# TestingChargeController.net
KiCad netlist of a schematic drawn in Altium Designer
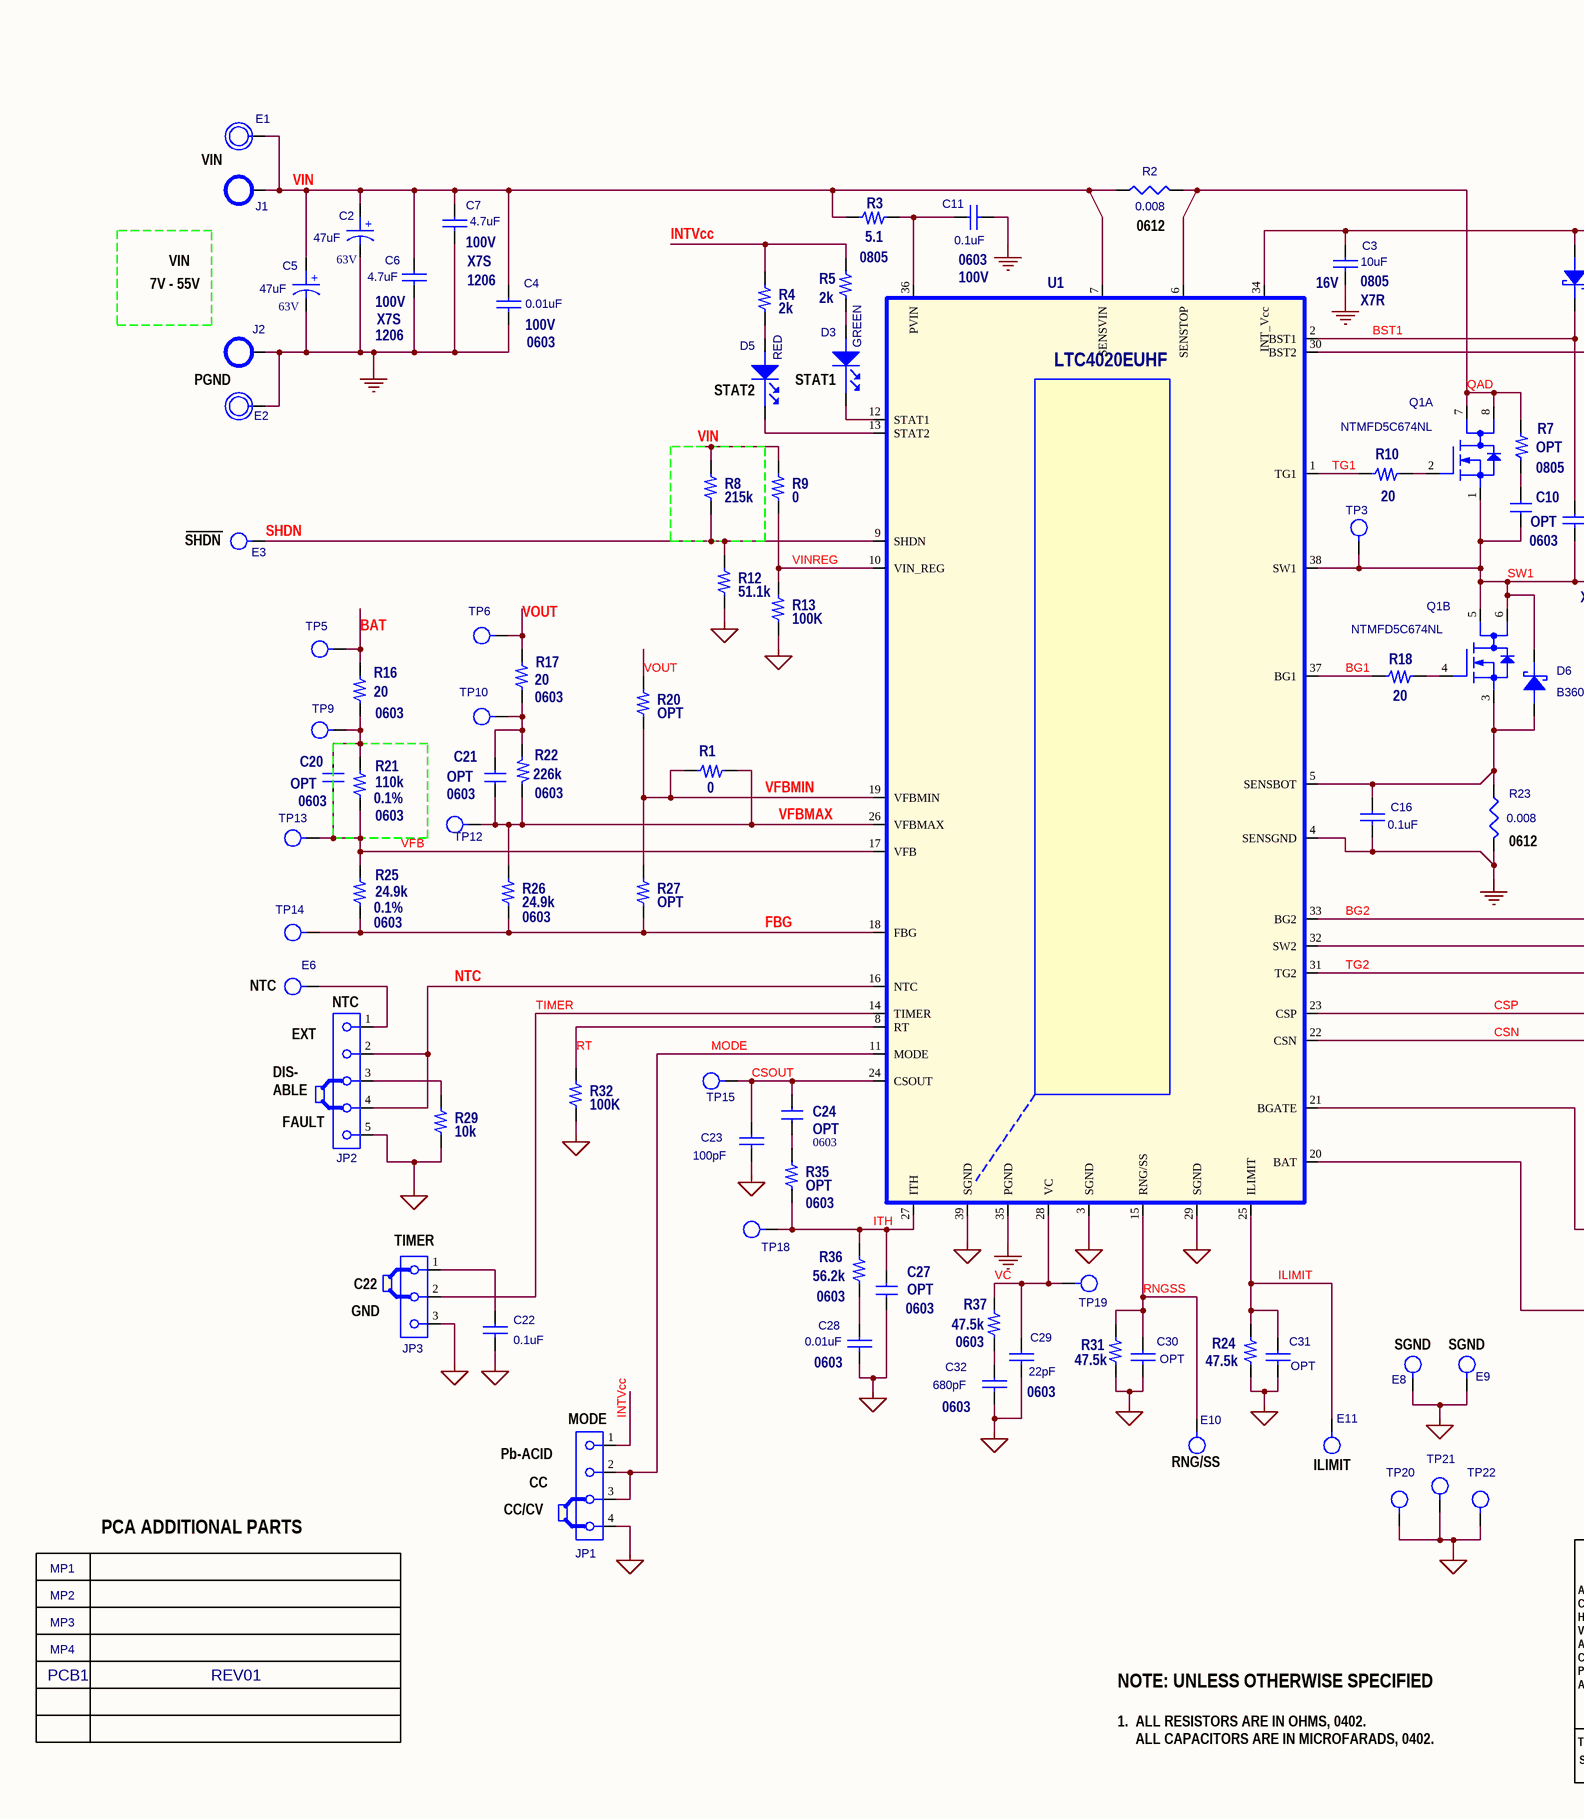
[diagram p0: TestingChargeController.SchDoc, left]
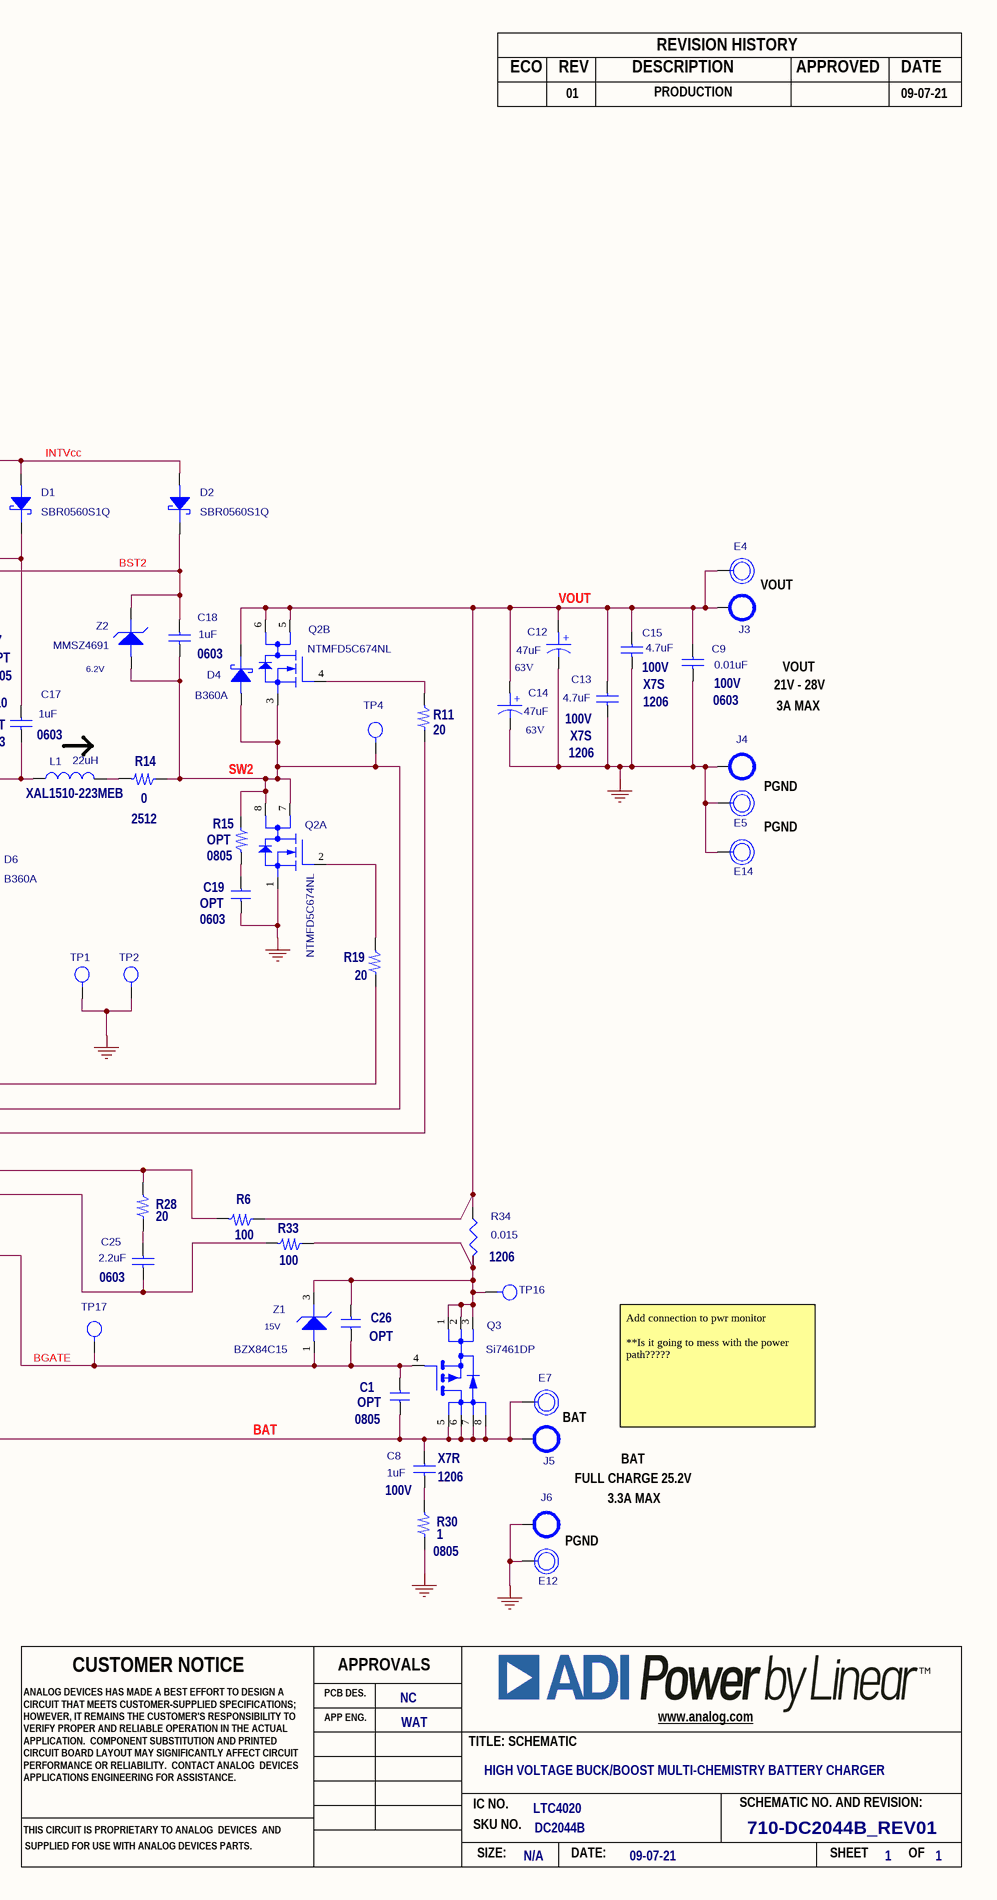
[diagram p1: TestingChargeController.SchDoc, right]

(export (version "E")
  (design (tool "Eeschema 10.0.6"))
  (components
    (comp (ref "*")
      (value "~")
      (fields
        (field (name "SKU#") "DC2044B")
        (field (name "SIZE") "N/A")
        (field (name "PAGE NUMBER") "1")
        (field (name "PAGE COUNT") "1")
        (field (name "PCB DESIGNER") "NC")
        (field (name "PCA SCHEMATIC") "710-DC2044B_REV01")
        (field (name "IC NO.") "LTC4020")
        (field (name "DATE") "09-07-21")
        (field (name "APP. ENG.") "WAT")
        (field (name "TITLE") "HIGH VOLTAGE BUCK/BOOST MULTI-CHEMISTRY BATTERY CHARGER")
      )
      (libsource (lib "*") (part "TITLEBLK_REV09_2"))
    )
    (comp (ref "C1")
      (value "OPT")
      (footprint "CC0805N")
      (description "CAP., OPTION, 0805")
      (fields (field (name "PACKAGE SIZE") "0805") (field (name "PART_NUMBER") "150-3036"))
      (libsource (lib "*") (part "CAP_ALT"))
    )
    (comp (ref "C2")
      (value "47uF")
      (footprint "PANASONIC_ZA_8X10.2")
      (description "CAP.,47uF,ALUM ELECT.,63V,20%,SMD,8.0x10.2 mm,AEC-Q200")
      (fields
        (field (name "PART_NUMBER") "150-0969")
        (field (name "TOLERANCE") "20%")
        (field (name "RATED VOLTAGE") "63V")
      )
      (libsource (lib "*") (part "CAP_P_ALT"))
    )
    (comp (ref "C3")
      (value "10uF")
      (footprint "CC0805N")
      (description "CAP.,10uF,X7R,16V,10%,0805")
      (fields
        (field (name "MANUFACTURER") "TAIYO YUDEN")
        (field (name "RATED VOLTAGE") "16V")
        (field (name "TOLERANCE") "10%")
        (field (name "DIELECTRIC TYPE") "X7R")
        (field (name "PACKAGE SIZE") "0805")
      )
      (libsource (lib "*") (part "CAP"))
    )
    (comp (ref "C4")
      (value "0.01uF")
      (footprint "CC0603N")
      (description "CAP.,0.01uF,X7R,100V,10%,0603,AEC-Q200")
      (fields
        (field (name "MANUFACTURER") "MURATA")
        (field (name "RATED VOLTAGE") "100V")
        (field (name "TOLERANCE") "10%")
        (field (name "PACKAGE SIZE") "0603")
      )
      (libsource (lib "*") (part "CAP"))
    )
    (comp (ref "C5")
      (value "47uF")
      (footprint "PANASONIC_ZA_8X10.2")
      (description "CAP.,47uF,ALUM ELECT.,63V,20%,SMD,8.0x10.2 mm,AEC-Q200")
      (fields
        (field (name "MANUFACTURER") "PANASONIC")
        (field (name "RATED VOLTAGE") "63V")
        (field (name "TOLERANCE") "20%")
      )
      (libsource (lib "*") (part "CAP_P_ALT"))
    )
    (comp (ref "C6")
      (value "4.7uF")
      (footprint "CC1206N")
      (description "CAP.,4.7uF,X7S,100V,20%,1206")
      (fields
        (field (name "PART_NUMBER") "150-2278")
        (field (name "PACKAGE SIZE") "1206")
        (field (name "DIELECTRIC TYPE") "X7S")
        (field (name "TOLERANCE") "20%")
        (field (name "RATED VOLTAGE") "100V")
      )
      (libsource (lib "*") (part "CAP"))
    )
    (comp (ref "C7")
      (value "4.7uF")
      (footprint "CC1206N")
      (description "CAP.,4.7uF,X7S,100V,20%,1206")
      (fields
        (field (name "PART_NUMBER") "150-2278")
        (field (name "PACKAGE SIZE") "1206")
        (field (name "DIELECTRIC TYPE") "X7S")
        (field (name "TOLERANCE") "20%")
        (field (name "RATED VOLTAGE") "100V")
      )
      (libsource (lib "*") (part "CAP"))
    )
    (comp (ref "C8")
      (value "1uF")
      (footprint "CC1206N")
      (description "CAP.,1uF,X7R,100V,10%,1206,AEC-Q200")
      (fields
        (field (name "MANUFACTURER") "TDK")
        (field (name "RATED VOLTAGE") "100V")
        (field (name "TOLERANCE") "10%")
        (field (name "TEMPERATURE COEFFICIENT") "X7R")
        (field (name "PACKAGE SIZE") "1206")
      )
      (libsource (lib "*") (part "CAP"))
    )
    (comp (ref "C9")
      (value "0.01uF")
      (footprint "CC0603N")
      (description "CAP.,0.01uF,X7R,100V,10%,0603,AEC-Q200")
      (fields
        (field (name "MANUFACTURER") "MURATA")
        (field (name "RATED VOLTAGE") "100V")
        (field (name "TOLERANCE") "10%")
        (field (name "PACKAGE SIZE") "0603")
      )
      (libsource (lib "*") (part "CAP"))
    )
    (comp (ref "C10")
      (value "OPT")
      (footprint "CC0603N")
      (description "CAP., OPTION, 0603")
      (fields (field (name "PACKAGE SIZE") "0603") (field (name "PART_NUMBER") "150-3038"))
      (libsource (lib "*") (part "CAP_ALT"))
    )
    (comp (ref "C11")
      (value "0.1uF")
      (footprint "CC0603N")
      (description "CAP.,0.1uF,X7R,100V,10%,0603,AEC-Q200")
      (fields
        (field (name "MANUFACTURER") "TAIYO YUDEN")
        (field (name "RATED VOLTAGE") "100V")
        (field (name "TOLERANCE") "10%")
        (field (name "PACKAGE SIZE") "0603")
      )
      (libsource (lib "*") (part "CAP"))
    )
    (comp (ref "C12")
      (value "47uF")
      (footprint "PANASONIC_ZA_8X10.2")
      (description "CAP.,47uF,ALUM ELECT.,63V,20%,SMD,8.0x10.2 mm,AEC-Q200")
      (fields
        (field (name "PART_NUMBER") "150-0969")
        (field (name "TOLERANCE") "20%")
        (field (name "RATED VOLTAGE") "63V")
      )
      (libsource (lib "*") (part "CAP_P_ALT"))
    )
    (comp (ref "C13")
      (value "4.7uF")
      (footprint "CC1206N")
      (description "CAP.,4.7uF,X7S,100V,20%,1206")
      (fields
        (field (name "MANUFACTURER") "AVX")
        (field (name "RATED VOLTAGE") "100V")
        (field (name "TOLERANCE") "20%")
        (field (name "DIELECTRIC TYPE") "X7S")
        (field (name "PACKAGE SIZE") "1206")
      )
      (libsource (lib "*") (part "CAP"))
    )
    (comp (ref "C14")
      (value "47uF")
      (footprint "PANASONIC_ZA_8X10.2")
      (description "CAP.,47uF,ALUM ELECT.,63V,20%,SMD,8.0x10.2 mm,AEC-Q200")
      (fields
        (field (name "PART_NUMBER") "150-0969")
        (field (name "TOLERANCE") "20%")
        (field (name "RATED VOLTAGE") "63V")
      )
      (libsource (lib "*") (part "CAP_P_ALT"))
    )
    (comp (ref "C15")
      (value "4.7uF")
      (footprint "CC1206N")
      (description "CAP.,4.7uF,X7S,100V,20%,1206")
      (fields
        (field (name "PART_NUMBER") "150-2278")
        (field (name "PACKAGE SIZE") "1206")
        (field (name "DIELECTRIC TYPE") "X7S")
        (field (name "TOLERANCE") "20%")
        (field (name "RATED VOLTAGE") "100V")
      )
      (libsource (lib "*") (part "CAP"))
    )
    (comp (ref "C16")
      (value "0.1uF")
      (footprint "CC0402N")
      (description "CAP.,0.1uF,X7R,16V,10%,0402,AEC-Q200")
      (fields (field (name "PART_NUMBER") "150-0506") (field (name "TOLERANCE") "10%"))
      (libsource (lib "*") (part "CAP"))
    )
    (comp (ref "C17")
      (value "1uF")
      (footprint "CC0603N")
      (description "CAP.,1uF,X7R,16V,10%,0603")
      (fields
        (field (name "MANUFACTURER") "KEMET")
        (field (name "TOLERANCE") "10%")
        (field (name "PACKAGE SIZE") "0603")
      )
      (libsource (lib "*") (part "CAP"))
    )
    (comp (ref "C18")
      (value "1uF")
      (footprint "CC0603N")
      (description "CAP.,1uF,X7R,16V,10%,0603")
      (fields
        (field (name "MANUFACTURER") "KEMET")
        (field (name "TOLERANCE") "10%")
        (field (name "PACKAGE SIZE") "0603")
      )
      (libsource (lib "*") (part "CAP"))
    )
    (comp (ref "C19")
      (value "OPT")
      (footprint "CC0603N")
      (description "CAP., OPTION, 0603")
      (fields (field (name "PACKAGE SIZE") "0603") (field (name "PART_NUMBER") "150-3038"))
      (libsource (lib "*") (part "CAP_ALT"))
    )
    (comp (ref "C20")
      (value "OPT")
      (footprint "CC0603N")
      (description "CAP., OPTION, 0603")
      (fields (field (name "PACKAGE SIZE") "0603") (field (name "PART_NUMBER") "150-3038"))
      (libsource (lib "*") (part "CAP_ALT"))
    )
    (comp (ref "C21")
      (value "OPT")
      (footprint "CC0603N")
      (description "CAP., OPTION, 0603")
      (fields (field (name "PACKAGE SIZE") "0603") (field (name "PART_NUMBER") "150-3038"))
      (libsource (lib "*") (part "CAP_ALT"))
    )
    (comp (ref "C22")
      (value "0.1uF")
      (footprint "CC0402N")
      (description "CAP.,0.1uF,X7R,16V,10%,0402,AEC-Q200")
      (fields (field (name "MANUFACTURER") "MURATA") (field (name "TOLERANCE") "10%"))
      (libsource (lib "*") (part "CAP"))
    )
    (comp (ref "C23")
      (value "100pF")
      (footprint "CC0402N")
      (description "CAP.,100pF,C0G,50V,5%,0402")
      (fields (field (name "PART_NUMBER") "150-0115") (field (name "TOLERANCE") "5%"))
      (libsource (lib "*") (part "CAP"))
    )
    (comp (ref "C24")
      (value "OPT")
      (footprint "CC0603N")
      (description "CAP., OPTION, 0603")
      (fields (field (name "PART_NUMBER") "150-3038") (field (name "PACKAGE SIZE") "0603"))
      (libsource (lib "*") (part "CAP_ALT"))
    )
    (comp (ref "C25")
      (value "2.2uF")
      (footprint "CC0603N")
      (description "CAP.,2.2uF,X7R,10V,10%,0603")
      (fields
        (field (name "MANUFACTURER") "MURATA")
        (field (name "TOLERANCE") "10%")
        (field (name "PACKAGE SIZE") "0603")
      )
      (libsource (lib "*") (part "CAP"))
    )
    (comp (ref "C26")
      (value "OPT")
      (footprint "CC0603N")
      (description "CAP., OPTION, 0603")
      (fields (field (name "PART_NUMBER") "150-3038"))
      (libsource (lib "*") (part "CAP_ALT"))
    )
    (comp (ref "C27")
      (value "OPT")
      (footprint "CC0603N")
      (description "CAP., OPTION, 0603")
      (fields (field (name "PART_NUMBER") "150-3038") (field (name "PACKAGE SIZE") "0603"))
      (libsource (lib "*") (part "CAP_ALT"))
    )
    (comp (ref "C28")
      (value "0.01uF")
      (footprint "CC0603N")
      (description "CAP.,0.01uF,X7R,50V,10%,0603")
      (fields
        (field (name "MANUFACTURER") "AVX")
        (field (name "TOLERANCE") "10%")
        (field (name "PACKAGE SIZE") "0603")
      )
      (libsource (lib "*") (part "CAP"))
    )
    (comp (ref "C29")
      (value "22pF")
      (footprint "CC0603N")
      (description "CAP.,22pF,C0G,25V,10%,0603")
      (fields
        (field (name "MANUFACTURER") "AVX")
        (field (name "TOLERANCE") "10%")
        (field (name "PACKAGE SIZE") "0603")
      )
      (libsource (lib "*") (part "CAP"))
    )
    (comp (ref "C30")
      (value "OPT")
      (footprint "CC0402N")
      (description "CAP., OPTION, 0402")
      (fields (field (name "PART_NUMBER") "150-3148"))
      (libsource (lib "*") (part "CAP"))
    )
    (comp (ref "C31")
      (value "OPT")
      (footprint "CC0402N")
      (description "CAP., OPTION, 0402")
      (fields (field (name "PART_NUMBER") "150-3148"))
      (libsource (lib "*") (part "CAP"))
    )
    (comp (ref "C32")
      (value "680pF")
      (footprint "CC0603N")
      (description "CAP.,680pF,C0G,25V,5%,0603")
      (fields
        (field (name "MANUFACTURER") "AVX")
        (field (name "TOLERANCE") "5%")
        (field (name "PACKAGE SIZE") "0603")
      )
      (libsource (lib "*") (part "CAP"))
    )
    (comp (ref "D1")
      (value "SBR0560S1Q")
      (footprint "SOD-123N")
      (description "DIODE,SBR,60V,500mA,SOD123")
      (fields (field (name "PART_NUMBER") "210-0561") (field (name "MANUFACTURER") "DIODES INC."))
      (libsource (lib "*") (part "DIODE_SCHOTTKY_A_ALT"))
    )
    (comp (ref "D2")
      (value "SBR0560S1Q")
      (footprint "SOD-123N")
      (description "DIODE,SBR,60V,500mA,SOD123")
      (fields (field (name "PART_NUMBER") "210-0561") (field (name "MANUFACTURER") "DIODES INC."))
      (libsource (lib "*") (part "DIODE_SCHOTTKY_A_ALT"))
    )
    (comp (ref "D3")
      (value "GREEN")
      (footprint "LED_0603")
      (description "LED,GREEN,WATER-CLEAR,0603")
      (fields (field (name "PART_NUMBER") "270-0051") (field (name "MANUFACTURER") "LITE-ON"))
      (libsource (lib "*") (part "LED_ALT"))
    )
    (comp (ref "D4")
      (value "B360A")
      (footprint "SMA-N")
      (description "DIODE,SCHOTTKY RECTIFIER,60V,3A,4.6mm X 2.92mm")
      (fields (field (name "MANUFACTURER") "DIODES INC.") (field (name "PART_NUMBER") "210-0103"))
      (libsource (lib "*") (part "DIODE_SCHOTTKY_A_ALT"))
    )
    (comp (ref "D5")
      (value "RED")
      (footprint "LED_0603")
      (description "LED,RED,WATER-CLEAR,0603")
      (fields (field (name "MANUFACTURER") "LITE-ON") (field (name "PART_NUMBER") "270-0070"))
      (libsource (lib "*") (part "LED_ALT"))
    )
    (comp (ref "D6")
      (value "B360A")
      (footprint "SMA-N")
      (description "DIODE,SCHOTTKY RECTIFIER,60V,3A,4.6mm X 2.92mm")
      (fields (field (name "PART_NUMBER") "210-0103") (field (name "MANUFACTURER") "DIODES INC."))
      (libsource (lib "*") (part "DIODE_SCHOTTKY_A_ALT"))
    )
    (comp (ref "E1")
      (value "TEST POINT")
      (footprint "MILLMAX2501")
      (description "TEST POINT,TURRET,0.094\" MTG. HOLE,PCB 0.062\" THK")
      (fields (field (name "MANUFACTURER") "MILL-MAX") (field (name "PART_NUMBER") "260-0003"))
      (libsource (lib "*") (part "TURRET_A"))
    )
    (comp (ref "E2")
      (value "TEST POINT")
      (footprint "MILLMAX2501")
      (description "TEST POINT,TURRET,0.094\" MTG. HOLE,PCB 0.062\" THK")
      (fields (field (name "MANUFACTURER") "MILL-MAX") (field (name "PART_NUMBER") "260-0003"))
      (libsource (lib "*") (part "TURRET_A"))
    )
    (comp (ref "E3")
      (value "TEST POINT")
      (footprint "MILLMAX2308")
      (description "TEST POINT,TURRET,0.064\" MTG. HOLE,PCB 0.062\" THK")
      (fields (field (name "PART_NUMBER") "260-0004") (field (name "MANUFACTURER") "MILL-MAX"))
      (libsource (lib "*") (part "TEST_POINT_.156_MILL-MAX_2308"))
    )
    (comp (ref "E4")
      (value "TEST POINT")
      (footprint "MILLMAX2501")
      (description "TEST POINT,TURRET,0.094\" MTG. HOLE,PCB 0.062\" THK")
      (fields (field (name "PART_NUMBER") "260-0003") (field (name "MANUFACTURER") "MILL-MAX"))
      (libsource (lib "*") (part "TURRET_A"))
    )
    (comp (ref "E5")
      (value "TEST POINT")
      (footprint "MILLMAX2501")
      (description "TEST POINT,TURRET,0.094\" MTG. HOLE,PCB 0.062\" THK")
      (fields (field (name "PART_NUMBER") "260-0003") (field (name "MANUFACTURER") "MILL-MAX"))
      (libsource (lib "*") (part "TURRET_A"))
    )
    (comp (ref "E6")
      (value "TEST POINT")
      (footprint "MILLMAX2308")
      (description "TEST POINT,TURRET,0.064\" MTG. HOLE,PCB 0.062\" THK")
      (fields (field (name "PART_NUMBER") "260-0004") (field (name "MANUFACTURER") "MILL-MAX"))
      (libsource (lib "*") (part "TEST_POINT_.156_MILL-MAX_2308"))
    )
    (comp (ref "E7")
      (value "TEST POINT")
      (footprint "MILLMAX2501")
      (description "TEST POINT,TURRET,0.094\" MTG. HOLE,PCB 0.062\" THK")
      (fields (field (name "PART_NUMBER") "260-0003") (field (name "MANUFACTURER") "MILL-MAX"))
      (libsource (lib "*") (part "TURRET_A"))
    )
    (comp (ref "E8")
      (value "TEST POINT")
      (footprint "MILLMAX2308")
      (description "TEST POINT,TURRET,0.064\" MTG. HOLE,PCB 0.062\" THK")
      (fields (field (name "MANUFACTURER") "MILL-MAX") (field (name "PART_NUMBER") "260-0004"))
      (libsource (lib "*") (part "TEST_POINT_.156_MILL-MAX_2308"))
    )
    (comp (ref "E9")
      (value "TEST POINT")
      (footprint "MILLMAX2308")
      (description "TEST POINT,TURRET,0.064\" MTG. HOLE,PCB 0.062\" THK")
      (fields (field (name "PART_NUMBER") "260-0004") (field (name "MANUFACTURER") "MILL-MAX"))
      (libsource (lib "*") (part "TEST_POINT_.156_MILL-MAX_2308"))
    )
    (comp (ref "E10")
      (value "TEST POINT")
      (footprint "MILLMAX2308")
      (description "TEST POINT,TURRET,0.064\" MTG. HOLE,PCB 0.062\" THK")
      (fields (field (name "MANUFACTURER") "MILL-MAX") (field (name "PART_NUMBER") "260-0004"))
      (libsource (lib "*") (part "TEST_POINT_.156_MILL-MAX_2308"))
    )
    (comp (ref "E11")
      (value "TEST POINT")
      (footprint "MILLMAX2308")
      (description "TEST POINT,TURRET,0.064\" MTG. HOLE,PCB 0.062\" THK")
      (fields (field (name "PART_NUMBER") "260-0004") (field (name "MANUFACTURER") "MILL-MAX"))
      (libsource (lib "*") (part "TEST_POINT_.156_MILL-MAX_2308"))
    )
    (comp (ref "E12")
      (value "TEST POINT")
      (footprint "MILLMAX2501")
      (description "TEST POINT,TURRET,0.094\" MTG. HOLE,PCB 0.062\" THK")
      (fields (field (name "MANUFACTURER") "MILL-MAX") (field (name "PART_NUMBER") "260-0003"))
      (libsource (lib "*") (part "TURRET_A"))
    )
    (comp (ref "E14")
      (value "TEST POINT")
      (footprint "MILLMAX2501")
      (description "TEST POINT,TURRET,0.094\" MTG. HOLE,PCB 0.062\" THK")
      (fields (field (name "PART_NUMBER") "260-0003") (field (name "MANUFACTURER") "MILL-MAX"))
      (libsource (lib "*") (part "TURRET_A"))
    )
    (comp (ref "J1")
      (value "BANANA JACK")
      (footprint "KEY-575-4")
      (description "CONN.,BANANA JACK,FEMALE,THT,NON-INSULATED,SWAGE,0.218\"")
      (fields (field (name "MANUFACTURER") "KEYSTONE") (field (name "PART_NUMBER") "250-0428"))
      (libsource (lib "*") (part "BANANA_KEYSTONE-575-4_C"))
    )
    (comp (ref "J2")
      (value "BANANA JACK")
      (footprint "KEY-575-4")
      (description "CONN.,BANANA JACK,FEMALE,THT,NON-INSULATED,SWAGE,0.218\"")
      (fields (field (name "PART_NUMBER") "250-0428") (field (name "MANUFACTURER") "KEYSTONE"))
      (libsource (lib "*") (part "BANANA_KEYSTONE-575-4_C"))
    )
    (comp (ref "J3")
      (value "BANANA JACK")
      (footprint "KEY-575-4")
      (description "CONN.,BANANA JACK,FEMALE,THT,NON-INSULATED,SWAGE,0.218\"")
      (fields (field (name "PART_NUMBER") "250-0428") (field (name "MANUFACTURER") "KEYSTONE"))
      (libsource (lib "*") (part "BANANA_KEYSTONE-575-4_C"))
    )
    (comp (ref "J4")
      (value "BANANA JACK")
      (footprint "KEY-575-4")
      (description "CONN.,BANANA JACK,FEMALE,THT,NON-INSULATED,SWAGE,0.218\"")
      (fields (field (name "MANUFACTURER") "KEYSTONE") (field (name "PART_NUMBER") "250-0428"))
      (libsource (lib "*") (part "BANANA_KEYSTONE-575-4_C"))
    )
    (comp (ref "J5")
      (value "BANANA JACK")
      (footprint "KEY-575-4")
      (description "CONN.,BANANA JACK,FEMALE,THT,NON-INSULATED,SWAGE,0.218\"")
      (fields (field (name "PART_NUMBER") "250-0428") (field (name "MANUFACTURER") "KEYSTONE"))
      (libsource (lib "*") (part "BANANA_KEYSTONE-575-4_C"))
    )
    (comp (ref "J6")
      (value "BANANA JACK")
      (footprint "KEY-575-4")
      (description "CONN.,BANANA JACK,FEMALE,THT,NON-INSULATED,SWAGE,0.218\"")
      (fields (field (name "MANUFACTURER") "KEYSTONE") (field (name "PART_NUMBER") "250-0428"))
      (libsource (lib "*") (part "BANANA_KEYSTONE-575-4_C"))
    )
    (comp (ref "JP1")
      (value "HDR")
      (footprint "HD1X4-079")
      (description "CONN.,HDR,MALE,1x4,2mm,VERT,ST,THT")
      (fields
        (field (name "MANUFACTURER") "SULLINS CONNECTOR SOLUTIONS")
        (field (name "PART_NUMBER") "250-0431")
      )
      (libsource (lib "*") (part "HDR1X4"))
    )
    (comp (ref "JP2")
      (value "HEADER")
      (footprint "HD1X5-079")
      (description "CONN.,HEADER,MALE,1X5,2mm,ST, THT")
      (fields
        (field (name "MANUFACTURER") "SULLINS CONNECTOR SOLUTIONS")
        (field (name "PART_NUMBER") "250-0564")
      )
      (libsource (lib "*") (part "HDR1X5"))
    )
    (comp (ref "JP3")
      (value "HDR")
      (footprint "HD1X3-079")
      (description "CONN.,HDR,MALE,1x3,2mm,VERT,ST,THT,NO SUBS. ALLOWED")
      (fields (field (name "MANUFACTURER") "SAMTEC") (field (name "PART_NUMBER") "250-0638"))
      (libsource (lib "*") (part "1X3"))
    )
    (comp (ref "L1")
      (value "22uH")
      (footprint "COILCRAFT-XAL1510")
      (description "IND.,22uH,PWR,20%,14A,16mOHMS,16.2x15.2mm,AEC-Q200")
      (fields
        (field (name "MANUFACTURER PN") "XAL1510-223MEB")
        (field (name "MANUFACTURER") "COILCRAFT")
        (field (name "TOLERANCE") "20%")
      )
      (libsource (lib "*") (part "IND_ALT"))
    )
    (comp (ref "MP1")
      (value "STANDOFF")
      (footprint "MTG-8831")
      (description "STANDOFF,NYLON,SNAP-ON,0.25\" (6.4mm)")
      (fields (field (name "MANUFACTURER") "KEYSTONE") (field (name "PART_NUMBER") "763-0006"))
      (libsource (lib "*") (part "BLANK_MECHANICAL_PART"))
    )
    (comp (ref "MP2")
      (value "STANDOFF")
      (footprint "MTG-8831")
      (description "STANDOFF,NYLON,SNAP-ON,0.25\" (6.4mm)")
      (fields (field (name "MANUFACTURER") "KEYSTONE") (field (name "PART_NUMBER") "763-0006"))
      (libsource (lib "*") (part "BLANK_MECHANICAL_PART"))
    )
    (comp (ref "MP3")
      (value "STANDOFF")
      (footprint "MTG-8831")
      (description "STANDOFF,NYLON,SNAP-ON,0.25\" (6.4mm)")
      (fields (field (name "MANUFACTURER") "KEYSTONE") (field (name "PART_NUMBER") "763-0006"))
      (libsource (lib "*") (part "BLANK_MECHANICAL_PART"))
    )
    (comp (ref "MP4")
      (value "STANDOFF")
      (footprint "MTG-8831")
      (description "STANDOFF,NYLON,SNAP-ON,0.25\" (6.4mm)")
      (fields (field (name "MANUFACTURER") "KEYSTONE") (field (name "PART_NUMBER") "763-0006"))
      (libsource (lib "*") (part "BLANK_MECHANICAL_PART"))
    )
    (comp (ref "PCB1")
      (value "PCB, DC2044B")
      (fields
        (field (name "BOM NOTES") "REV01")
        (field (name "PART_NUMBER") "600-DC2044B")
        (field (name "MANUFACTURER") "ADI APPROVED SUPPLIER")
      )
      (libsource (lib "*") (part "BLANK_PCB_PART"))
    )
    (comp (ref "Q1")
      (value "NTMFD5C674NL")
      (footprint "ONSEMI-DFN8-SO-8FL")
      (description "XSTR.,MOSFET,DUAL N-CH,60V,42A,DFN-8 (SO8FL)")
      (fields (field (name "PART_NUMBER") "240-0596") (field (name "MANUFACTURER") "ON Semiconductor"))
      (libsource (lib "*") (part "DUAL_8P_N-CH_TYPE1A"))
    )
    (comp (ref "Q2")
      (value "NTMFD5C674NL")
      (footprint "ONSEMI-DFN8-SO-8FL")
      (description "XSTR.,MOSFET,DUAL N-CH,60V,42A,DFN-8 (SO8FL)")
      (fields (field (name "MANUFACTURER") "ON Semiconductor") (field (name "PART_NUMBER") "240-0596"))
      (libsource (lib "*") (part "DUAL_8P_N-CH_TYPE1A"))
    )
    (comp (ref "Q3")
      (value "Si7461DP")
      (footprint "VISHAY_PPAK_SO-8")
      (description "XSTR.,MOSFET, P-CH,60V,8.6A,PowerPAK SO-8")
      (fields (field (name "MANUFACTURER") "VISHAY") (field (name "PART_NUMBER") "240-0180"))
      (libsource (lib "*") (part "8P_P-CH_TYPE1A"))
    )
    (comp (ref "R1")
      (value "0")
      (footprint "CR0402N")
      (description "RES.,0 OHM,1/16W,0402")
      (fields (field (name "PART_NUMBER") "100-0215") (field (name "MANUFACTURER") "ROHM"))
      (libsource (lib "*") (part "RES_ALT"))
    )
    (comp (ref "R2")
      (value "0.008")
      (footprint "SUSUMU-PRL1632")
      (description "RES.,0.008 OHMS,1%,1W,1206,LONG-SIDE,SENSE")
      (fields (field (name "MANUFACTURER") "Susumu") (field (name "TOLERANCE") "1%"))
      (libsource (lib "*") (part "RES"))
    )
    (comp (ref "R3")
      (value "5.1")
      (footprint "CR0805N")
      (description "RES.,5.1 OHMS,5%,1/8W,0805,AEC-Q200")
      (fields
        (field (name "PART_NUMBER") "100-2080")
        (field (name "PACKAGE SIZE") "0805")
        (field (name "TOLERANCE") "5%")
      )
      (libsource (lib "*") (part "RES_ALT"))
    )
    (comp (ref "R4")
      (value "2k")
      (footprint "CR0402N")
      (description "RES.,2k OHMS,1%,1/16W,0402,AEC-Q200")
      (fields (field (name "MANUFACTURER") "VISHAY") (field (name "TOLERANCE") "1%"))
      (libsource (lib "*") (part "RES_ALT"))
    )
    (comp (ref "R5")
      (value "2k")
      (footprint "CR0402N")
      (description "RES.,2k OHMS,1%,1/16W,0402,AEC-Q200")
      (fields (field (name "PART_NUMBER") "100-0018") (field (name "TOLERANCE") "1%"))
      (libsource (lib "*") (part "RES_ALT"))
    )
    (comp (ref "R6")
      (value "100")
      (footprint "CR0402N")
      (description "RES.,100 OHMS,1%,1/16W,0402,AEC-Q200")
      (fields (field (name "MANUFACTURER") "KOA SPEER") (field (name "TOLERANCE") "1%"))
      (libsource (lib "*") (part "RES_ALT"))
    )
    (comp (ref "R7")
      (value "OPT")
      (footprint "CR0805M")
      (description "RES., OPTION, 0805")
      (fields (field (name "PACKAGE SIZE") "0805") (field (name "PART_NUMBER") "100-2558"))
      (libsource (lib "*") (part "RES_ALT"))
    )
    (comp (ref "R8")
      (value "215k")
      (footprint "CR0402N")
      (description "RES.,215k OHMS,1%,1/16W,0402,AEC-Q200")
      (fields (field (name "MANUFACTURER") "NIC") (field (name "TOLERANCE") "1%"))
      (libsource (lib "*") (part "RES_ALT"))
    )
    (comp (ref "R9")
      (value "0")
      (footprint "CR0402N")
      (description "RES.,0 OHM,1/16W,0402")
      (fields (field (name "MANUFACTURER") "ROHM") (field (name "PART_NUMBER") "100-0215"))
      (libsource (lib "*") (part "RES_ALT"))
    )
    (comp (ref "R10")
      (value "20")
      (footprint "CR0402N")
      (description "RES.,20 OHMS,1%,1/16W,0402")
      (fields (field (name "MANUFACTURER") "VISHAY") (field (name "TOLERANCE") "1%"))
      (libsource (lib "*") (part "RES_ALT"))
    )
    (comp (ref "R11")
      (value "20")
      (footprint "CR0402N")
      (description "RES.,20 OHMS,1%,1/16W,0402")
      (fields (field (name "MANUFACTURER") "VISHAY") (field (name "TOLERANCE") "1%"))
      (libsource (lib "*") (part "RES_ALT"))
    )
    (comp (ref "R12")
      (value "51.1k")
      (footprint "CR0402N")
      (description "RES.,51.1k OHMS,1%,1/16W,0402,AEC-Q200")
      (fields (field (name "MANUFACTURER") "STACKPOLE ELECTRONICS, INC.") (field (name "TOLERANCE") "1%"))
      (libsource (lib "*") (part "RES_ALT"))
    )
    (comp (ref "R13")
      (value "100K")
      (footprint "CR0402N")
      (description "RES.,100k OHMS,1%,1/16W,0402,AEC-Q200")
      (fields (field (name "PART_NUMBER") "100-0601") (field (name "TOLERANCE") "1%"))
      (libsource (lib "*") (part "RES_ALT"))
    )
    (comp (ref "R14")
      (value "0")
      (footprint "VISHAY-WSL_9-2512")
      (description "RES.,0 OHM,200A,2512,COPPER,SENSE")
      (fields
        (field (name "MANUFACTURER") "VISHAY")
        (field (name "PACKAGE SIZE") "2512")
        (field (name "PART_NUMBER") "100-0588")
      )
      (libsource (lib "*") (part "RES_ALT"))
    )
    (comp (ref "R15")
      (value "OPT")
      (footprint "CR0805M")
      (description "RES., OPTION, 0805")
      (fields (field (name "PART_NUMBER") "100-2558") (field (name "PACKAGE SIZE") "0805"))
      (libsource (lib "*") (part "RES_ALT"))
    )
    (comp (ref "R16")
      (value "20")
      (footprint "CR0603N")
      (description "RES.,20 OHMS,1%,1/10W,0603")
      (fields
        (field (name "PART_NUMBER") "100-0703")
        (field (name "PACKAGE SIZE") "0603")
        (field (name "TOLERANCE") "1%")
      )
      (libsource (lib "*") (part "RES_ALT"))
    )
    (comp (ref "R17")
      (value "20")
      (footprint "CR0603N")
      (description "RES.,20 OHMS,1%,1/10W,0603")
      (fields
        (field (name "PART_NUMBER") "100-0703")
        (field (name "PACKAGE SIZE") "0603")
        (field (name "TOLERANCE") "1%")
      )
      (libsource (lib "*") (part "RES_ALT"))
    )
    (comp (ref "R18")
      (value "20")
      (footprint "CR0402N")
      (description "RES.,20 OHMS,1%,1/16W,0402")
      (fields (field (name "MANUFACTURER") "VISHAY") (field (name "TOLERANCE") "1%"))
      (libsource (lib "*") (part "RES_ALT"))
    )
    (comp (ref "R19")
      (value "20")
      (footprint "CR0402N")
      (description "RES.,20 OHMS,1%,1/16W,0402")
      (fields (field (name "MANUFACTURER") "VISHAY") (field (name "TOLERANCE") "1%"))
      (libsource (lib "*") (part "RES_ALT"))
    )
    (comp (ref "R20")
      (value "OPT")
      (footprint "CR0402N")
      (description "RES., OPTION, 0402")
      (fields (field (name "PART_NUMBER") "100-0357"))
      (libsource (lib "*") (part "RES_ALT"))
    )
    (comp (ref "R21")
      (value "110k")
      (footprint "CR0603N")
      (description "RES.,110k OHMS,0.1%,1/10W,0603,High Stability")
      (fields
        (field (name "PART_NUMBER") "100-2083")
        (field (name "PACKAGE SIZE") "0603")
        (field (name "TOLERANCE") "0.1%")
        (field (name "MANUFACTURER") "VISHAY")
      )
      (libsource (lib "*") (part "RES_ALT"))
    )
    (comp (ref "R22")
      (value "226k")
      (footprint "CR0603N")
      (description "RES.,226k OHMS,1%,1/10W,0603")
      (fields
        (field (name "PART_NUMBER") "100-2671")
        (field (name "PACKAGE SIZE") "0603")
        (field (name "TOLERANCE") "1%")
      )
      (libsource (lib "*") (part "RES_ALT"))
    )
    (comp (ref "R23")
      (value "0.008")
      (footprint "SUSUMU-PRL1632")
      (description "RES.,0.008 OHMS,1%,1W,1206,LONG-SIDE,SENSE")
      (fields (field (name "MANUFACTURER") "Susumu") (field (name "TOLERANCE") "1%"))
      (libsource (lib "*") (part "RES"))
    )
    (comp (ref "R24")
      (value "47.5k")
      (footprint "CR0402N")
      (description "RES.,47.5k OHMS,1%,1/16W,0402")
      (fields (field (name "PART_NUMBER") "100-0390") (field (name "TOLERANCE") "1%"))
      (libsource (lib "*") (part "RES_ALT"))
    )
    (comp (ref "R25")
      (value "24.9k")
      (footprint "CR0603N")
      (description "RES.,24.9k OHMS,0.1%,1/8W,0603,AEC-Q00")
      (fields
        (field (name "PART_NUMBER") "100-1806")
        (field (name "PACKAGE SIZE") "0603")
        (field (name "TOLERANCE") "0.1%")
        (field (name "MANUFACTURER") "VISHAY")
      )
      (libsource (lib "*") (part "RES_ALT"))
    )
    (comp (ref "R26")
      (value "24.9k")
      (footprint "CR0603N")
      (description "RES.,24.9k OHMS,1%,1/10W,0603,AEC-Q200")
      (fields
        (field (name "PART_NUMBER") "100-0037")
        (field (name "PACKAGE SIZE") "0603")
        (field (name "TOLERANCE") "1%")
      )
      (libsource (lib "*") (part "RES_ALT"))
    )
    (comp (ref "R27")
      (value "OPT")
      (footprint "CR0402N")
      (description "RES., OPTION, 0402")
      (fields (field (name "PART_NUMBER") "100-0357"))
      (libsource (lib "*") (part "RES_ALT"))
    )
    (comp (ref "R28")
      (value "20")
      (footprint "CR0402N")
      (description "RES.,20 OHMS,1%,1/16W,0402,AEC-Q200")
      (fields (field (name "MANUFACTURER") "NIC") (field (name "TOLERANCE") "1%"))
      (libsource (lib "*") (part "RES_ALT"))
    )
    (comp (ref "R29")
      (value "10k")
      (footprint "CR0402N")
      (description "RES.,10k OHMS,1%,1/10W,0402,AEC-Q200")
      (fields (field (name "MANUFACTURER") "KOA SPEER") (field (name "TOLERANCE") "1%"))
      (libsource (lib "*") (part "RES_ALT"))
    )
    (comp (ref "R30")
      (value "1")
      (footprint "CR0805M")
      (description "RES.,1 OHM,1%,1/8W,0805,AEC-Q200")
      (fields
        (field (name "MANUFACTURER") "VISHAY")
        (field (name "TOLERANCE") "1%")
        (field (name "PACKAGE SIZE") "0805")
      )
      (libsource (lib "*") (part "RES_ALT"))
    )
    (comp (ref "R31")
      (value "47.5k")
      (footprint "CR0402N")
      (description "RES.,47.5k OHMS,1%,1/16W,0402")
      (fields (field (name "MANUFACTURER") "NIC") (field (name "TOLERANCE") "1%"))
      (libsource (lib "*") (part "RES_ALT"))
    )
    (comp (ref "R32")
      (value "100K")
      (footprint "CR0402N")
      (description "RES.,100k OHMS,1%,1/16W,0402,AEC-Q200")
      (fields (field (name "PART_NUMBER") "100-0601") (field (name "TOLERANCE") "1%"))
      (libsource (lib "*") (part "RES_ALT"))
    )
    (comp (ref "R33")
      (value "100")
      (footprint "CR0402N")
      (description "RES.,100 OHMS,1%,1/16W,0402,AEC-Q200")
      (fields (field (name "MANUFACTURER") "KOA SPEER") (field (name "TOLERANCE") "1%"))
      (libsource (lib "*") (part "RES_ALT"))
    )
    (comp (ref "R34")
      (value "0.015")
      (footprint "SUSUMU-KRL1632")
      (description "RES.,0.015 OHMS,1%,3/4W,1206,AEC-Q200,METAL,SENSE")
      (fields
        (field (name "MANUFACTURER") "SUSUMU")
        (field (name "TOLERANCE") "1%")
        (field (name "PACKAGE SIZE") "1206")
      )
      (libsource (lib "*") (part "RES"))
    )
    (comp (ref "R35")
      (value "OPT")
      (footprint "CR0603N")
      (description "RES., OPTION, 0603")
      (fields (field (name "PACKAGE SIZE") "0603") (field (name "PART_NUMBER") "100-2374"))
      (libsource (lib "*") (part "RES_ALT"))
    )
    (comp (ref "R36")
      (value "56.2k")
      (footprint "CR0603N")
      (description "RES.,56.2k OHMS,1%,1/10W,0603,AEC-Q200")
      (fields
        (field (name "MANUFACTURER") "NIC")
        (field (name "TOLERANCE") "1%")
        (field (name "PACKAGE SIZE") "0603")
      )
      (libsource (lib "*") (part "RES_ALT"))
    )
    (comp (ref "R37")
      (value "47.5k")
      (footprint "CR0603N")
      (description "RES.,47.5k OHMS,1%,1/10W,0603")
      (fields
        (field (name "PART_NUMBER") "100-2554")
        (field (name "PACKAGE SIZE") "0603")
        (field (name "TOLERANCE") "1%")
      )
      (libsource (lib "*") (part "RES_ALT"))
    )
    (comp (ref "TP1")
      (value "TEST PAD")
      (footprint "PADSTYLE1")
      (description "TESTPOINT, PCB COPPER FEATURE")
      (fields (field (name "PART_NUMBER") "PCBPADS-8"))
      (libsource (lib "*") (part "PAD_STYLE_C"))
    )
    (comp (ref "TP2")
      (value "TEST PAD")
      (footprint "PADSTYLE1")
      (description "TESTPOINT, PCB COPPER FEATURE")
      (fields (field (name "PART_NUMBER") "PCBPADS-8"))
      (libsource (lib "*") (part "PAD_STYLE_C"))
    )
    (comp (ref "TP3")
      (value "TEST PAD")
      (footprint "PADSTYLE1")
      (description "TESTPOINT, PCB COPPER FEATURE")
      (fields (field (name "PART_NUMBER") "PCBPADS-8"))
      (libsource (lib "*") (part "PAD_STYLE_C"))
    )
    (comp (ref "TP4")
      (value "TEST PAD")
      (footprint "PADSTYLE1")
      (description "TESTPOINT, PCB COPPER FEATURE")
      (fields (field (name "PART_NUMBER") "PCBPADS-8"))
      (libsource (lib "*") (part "PAD_STYLE_C"))
    )
    (comp (ref "TP5")
      (value "TEST PAD")
      (footprint "PADSTYLE1")
      (description "TESTPOINT, PCB COPPER FEATURE")
      (fields (field (name "PART_NUMBER") "PCBPADS-8"))
      (libsource (lib "*") (part "PAD_STYLE_C"))
    )
    (comp (ref "TP6")
      (value "TEST PAD")
      (footprint "PADSTYLE1")
      (description "TESTPOINT, PCB COPPER FEATURE")
      (fields (field (name "PART_NUMBER") "PCBPADS-8"))
      (libsource (lib "*") (part "PAD_STYLE_C"))
    )
    (comp (ref "TP9")
      (value "TEST PAD")
      (footprint "PADSTYLE1")
      (description "TESTPOINT, PCB COPPER FEATURE")
      (fields (field (name "PART_NUMBER") "PCBPADS-8"))
      (libsource (lib "*") (part "PAD_STYLE_C"))
    )
    (comp (ref "TP10")
      (value "TEST PAD")
      (footprint "PADSTYLE1")
      (description "TESTPOINT, PCB COPPER FEATURE")
      (fields (field (name "PART_NUMBER") "PCBPADS-8"))
      (libsource (lib "*") (part "PAD_STYLE_C"))
    )
    (comp (ref "TP12")
      (value "TEST PAD")
      (footprint "PADSTYLE1")
      (description "TESTPOINT, PCB COPPER FEATURE")
      (fields (field (name "PART_NUMBER") "PCBPADS-8"))
      (libsource (lib "*") (part "PAD_STYLE_C"))
    )
    (comp (ref "TP13")
      (value "TEST PAD")
      (footprint "PADSTYLE1")
      (description "TESTPOINT, PCB COPPER FEATURE")
      (fields (field (name "PART_NUMBER") "PCBPADS-8"))
      (libsource (lib "*") (part "PAD_STYLE_C"))
    )
    (comp (ref "TP14")
      (value "TEST PAD")
      (footprint "PADSTYLE1")
      (description "TESTPOINT, PCB COPPER FEATURE")
      (fields (field (name "PART_NUMBER") "PCBPADS-8"))
      (libsource (lib "*") (part "PAD_STYLE_C"))
    )
    (comp (ref "TP15")
      (value "TEST PAD")
      (footprint "PADSTYLE1")
      (description "TESTPOINT, PCB COPPER FEATURE")
      (fields (field (name "PART_NUMBER") "PCBPADS-8"))
      (libsource (lib "*") (part "PAD_STYLE_C"))
    )
    (comp (ref "TP16")
      (value "TEST PAD")
      (footprint "PADSTYLE1")
      (description "TESTPOINT, PCB COPPER FEATURE")
      (fields (field (name "PART_NUMBER") "PCBPADS-8"))
      (libsource (lib "*") (part "PAD_STYLE_C"))
    )
    (comp (ref "TP17")
      (value "TEST PAD")
      (footprint "PADSTYLE1")
      (description "TESTPOINT, PCB COPPER FEATURE")
      (fields (field (name "PART_NUMBER") "PCBPADS-8"))
      (libsource (lib "*") (part "PAD_STYLE_C"))
    )
    (comp (ref "TP18")
      (value "TEST PAD")
      (footprint "PADSTYLE1")
      (description "TESTPOINT, PCB COPPER FEATURE")
      (fields (field (name "PART_NUMBER") "PCBPADS-8"))
      (libsource (lib "*") (part "PAD_STYLE_C"))
    )
    (comp (ref "TP19")
      (value "TEST PAD")
      (footprint "PADSTYLE1")
      (description "TESTPOINT, PCB COPPER FEATURE")
      (fields (field (name "PART_NUMBER") "PCBPADS-8"))
      (libsource (lib "*") (part "PAD_STYLE_C"))
    )
    (comp (ref "TP20")
      (value "TEST PAD")
      (footprint "PADSTYLE1")
      (description "TESTPOINT, PCB COPPER FEATURE")
      (fields (field (name "PART_NUMBER") "PCBPADS-8"))
      (libsource (lib "*") (part "PAD_STYLE_C"))
    )
    (comp (ref "TP21")
      (value "TEST PAD")
      (footprint "PADSTYLE1")
      (description "TESTPOINT, PCB COPPER FEATURE")
      (fields (field (name "PART_NUMBER") "PCBPADS-8"))
      (libsource (lib "*") (part "PAD_STYLE_C"))
    )
    (comp (ref "TP22")
      (value "TEST PAD")
      (footprint "PADSTYLE1")
      (description "TESTPOINT, PCB COPPER FEATURE")
      (fields (field (name "PART_NUMBER") "PCBPADS-8"))
      (libsource (lib "*") (part "PAD_STYLE_C"))
    )
    (comp (ref "U1")
      (value "LTC4020EUHF")
      (footprint "LTC-QFN-38-1701")
      (description "IC,55V BUCK-BOOST BATTERY CHARGER,38-pin QFN")
      (fields (field (name "MANUFACTURER") "LINEAR TECH.") (field (name "PART_NUMBER") "LTC4020EUHF#PBF"))
      (libsource (lib "*") (part "LTC4020EUHF"))
    )
    (comp (ref "XJP1")
      (value "SHUNT")
      (footprint "SAMTEC-SHUNT-079")
      (description "CONN.,SHUNT,FEMALE,2-POS,2mm")
      (fields (field (name "PART_NUMBER") "250-0419") (field (name "MANUFACTURER") "SAMTEC"))
      (libsource (lib "*") (part "SHUNT_2MM"))
    )
    (comp (ref "XJP2")
      (value "SHUNT")
      (footprint "SAMTEC-SHUNT-079")
      (description "CONN.,SHUNT,FEMALE,2-POS,2mm")
      (fields (field (name "MANUFACTURER") "SAMTEC") (field (name "PART_NUMBER") "250-0419"))
      (libsource (lib "*") (part "SHUNT_2MM"))
    )
    (comp (ref "XJP3")
      (value "SHUNT")
      (footprint "SAMTEC-SHUNT-079")
      (description "CONN.,SHUNT,FEMALE,2-POS,2mm")
      (fields (field (name "PART_NUMBER") "250-0419") (field (name "MANUFACTURER") "SAMTEC"))
      (libsource (lib "*") (part "SHUNT_2MM"))
    )
    (comp (ref "Z1")
      (value "BZX84C15")
      (footprint "SOT23-3N")
      (description "DIODE,ZENER,15V,350mW,SOT-23,AEC-Q101")
      (fields
        (field (name "RATED VOLTAGE OR ZENER VOLTAGE") "15V")
        (field (name "PART_NUMBER") "210-0510")
        (field (name "MANUFACTURER") "NEXPERIA")
      )
      (libsource (lib "*") (part "ZENER_SOT"))
    )
    (comp (ref "Z2")
      (value "MMSZ4691")
      (footprint "SOD-123N")
      (description "DIODE,ZENER,6.2V,500mW,SOD-123,AEC-Q101")
      (fields
        (field (name "RATED VOLTAGE OR ZENER VOLTAGE") "6.2V")
        (field (name "MANUFACTURER") "VISHAY")
        (field (name "PART_NUMBER") "210-0562")
      )
      (libsource (lib "*") (part "ZENER_ALT"))
    )
  )
  (nets
    (net (code "1") (name "/BAT") (class "Default")
      (node (ref "C1") (pin "2") (pinfunction "2_2") (pintype "passive"))
      (node (ref "C8") (pin "1") (pinfunction "1_1") (pintype "passive"))
      (node (ref "E7") (pin "1") (pinfunction "1_1") (pintype "passive"))
      (node (ref "J5") (pin "1") (pinfunction "1_1") (pintype "passive"))
      (node (ref "Q3") (pin "5") (pinfunction "D_5_5") (pintype "passive"))
      (node (ref "Q3") (pin "6") (pinfunction "D_6_6") (pintype "passive"))
      (node (ref "Q3") (pin "7") (pinfunction "D_7_7") (pintype "passive"))
      (node (ref "Q3") (pin "8") (pinfunction "D_8_8") (pintype "passive"))
      (node (ref "R16") (pin "1") (pinfunction "1_1") (pintype "passive"))
      (node (ref "TP5") (pin "1") (pinfunction "1_1") (pintype "passive"))
      (node (ref "U1") (pin "20") (pinfunction "BAT_20") (pintype "passive"))
    )
    (net (code "2") (name "/BG1") (class "Default")
      (node (ref "R18") (pin "1") (pinfunction "1_1") (pintype "passive"))
      (node (ref "U1") (pin "37") (pinfunction "BG1_37") (pintype "passive"))
    )
    (net (code "3") (name "/BG2") (class "Default")
      (node (ref "R19") (pin "2") (pinfunction "2_2") (pintype "passive"))
      (node (ref "U1") (pin "33") (pinfunction "BG2_33") (pintype "passive"))
    )
    (net (code "4") (name "/BGATE") (class "Default")
      (node (ref "C1") (pin "1") (pinfunction "1_1") (pintype "passive"))
      (node (ref "C26") (pin "2") (pinfunction "2_2") (pintype "passive"))
      (node (ref "Q3") (pin "4") (pinfunction "G_4") (pintype "passive"))
      (node (ref "TP17") (pin "1") (pinfunction "1_1") (pintype "passive"))
      (node (ref "U1") (pin "21") (pinfunction "BGATE_21") (pintype "passive"))
      (node (ref "Z1") (pin "1") (pinfunction "A_1") (pintype "passive"))
    )
    (net (code "5") (name "/BST1") (class "Default")
      (node (ref "C17") (pin "1") (pinfunction "1_1") (pintype "passive"))
      (node (ref "D1") (pin "1") (pinfunction "C_1") (pintype "passive"))
      (node (ref "U1") (pin "2") (pinfunction "BST1_2") (pintype "passive"))
    )
    (net (code "6") (name "/BST2") (class "Default")
      (node (ref "C18") (pin "1") (pinfunction "1_1") (pintype "passive"))
      (node (ref "D2") (pin "1") (pinfunction "C_1") (pintype "passive"))
      (node (ref "U1") (pin "30") (pinfunction "BST2_30") (pintype "passive"))
      (node (ref "Z2") (pin "1") (pinfunction "C_1") (pintype "passive"))
    )
    (net (code "7") (name "/CSN") (class "Default")
      (node (ref "C25") (pin "2") (pinfunction "2_2") (pintype "passive"))
      (node (ref "R33") (pin "1") (pinfunction "1_1") (pintype "passive"))
      (node (ref "U1") (pin "22") (pinfunction "CSN_22") (pintype "passive"))
    )
    (net (code "8") (name "/CSOUT") (class "Default")
      (node (ref "C23") (pin "1") (pinfunction "1_1") (pintype "passive"))
      (node (ref "C24") (pin "1") (pinfunction "1_1") (pintype "passive"))
      (node (ref "TP15") (pin "1") (pinfunction "1_1") (pintype "passive"))
      (node (ref "U1") (pin "24") (pinfunction "CSOUT_24") (pintype "passive"))
    )
    (net (code "9") (name "/CSP") (class "Default")
      (node (ref "R28") (pin "1") (pinfunction "1_1") (pintype "passive"))
      (node (ref "R6") (pin "1") (pinfunction "1_1") (pintype "passive"))
      (node (ref "U1") (pin "23") (pinfunction "CSP_23") (pintype "passive"))
    )
    (net (code "10") (name "/FBG") (class "Default")
      (node (ref "R25") (pin "2") (pinfunction "2_2") (pintype "passive"))
      (node (ref "R26") (pin "2") (pinfunction "2_2") (pintype "passive"))
      (node (ref "R27") (pin "2") (pinfunction "2_2") (pintype "passive"))
      (node (ref "TP14") (pin "1") (pinfunction "1_1") (pintype "passive"))
      (node (ref "U1") (pin "18") (pinfunction "FBG_18") (pintype "passive"))
    )
    (net (code "11") (name "/ILIMIT") (class "Default")
      (node (ref "C31") (pin "1") (pinfunction "1_1") (pintype "passive"))
      (node (ref "E11") (pin "1") (pinfunction "A_1") (pintype "passive"))
      (node (ref "R24") (pin "1") (pinfunction "1_1") (pintype "passive"))
      (node (ref "U1") (pin "25") (pinfunction "ILIMIT_25") (pintype "passive"))
    )
    (net (code "12") (name "/INTVcc") (class "Default")
      (node (ref "C3") (pin "1") (pinfunction "1_1") (pintype "passive"))
      (node (ref "D1") (pin "2") (pinfunction "A_2") (pintype "passive"))
      (node (ref "D2") (pin "2") (pinfunction "A_2") (pintype "passive"))
      (node (ref "JP1") (pin "1") (pinfunction "1_1") (pintype "passive"))
      (node (ref "R4") (pin "1") (pinfunction "1_1") (pintype "passive"))
      (node (ref "R5") (pin "1") (pinfunction "1_1") (pintype "passive"))
      (node (ref "U1") (pin "34") (pinfunction "INT_Vcc_34") (pintype "passive"))
    )
    (net (code "13") (name "/ITH") (class "Default")
      (node (ref "C27") (pin "1") (pinfunction "1_1") (pintype "passive"))
      (node (ref "R35") (pin "2") (pinfunction "2_2") (pintype "passive"))
      (node (ref "R36") (pin "1") (pinfunction "1_1") (pintype "passive"))
      (node (ref "TP18") (pin "1") (pinfunction "1_1") (pintype "passive"))
      (node (ref "U1") (pin "27") (pinfunction "ITH_27") (pintype "passive"))
    )
    (net (code "14") (name "/MODE") (class "Default")
      (node (ref "JP1") (pin "2") (pinfunction "2_2") (pintype "passive"))
      (node (ref "JP1") (pin "3") (pinfunction "3_3") (pintype "passive"))
      (node (ref "U1") (pin "11") (pinfunction "MODE_11") (pintype "passive"))
    )
    (net (code "15") (name "/NTC") (class "Default")
      (node (ref "JP2") (pin "2") (pinfunction "2_2") (pintype "passive"))
      (node (ref "JP2") (pin "4") (pinfunction "4_4") (pintype "passive"))
      (node (ref "U1") (pin "16") (pinfunction "NTC_16") (pintype "passive"))
    )
    (net (code "16") (name "/QAD") (class "Default")
      (node (ref "Q1") (pin "7") (pinfunction "D1_7_7") (pintype "passive"))
      (node (ref "Q1") (pin "8") (pinfunction "D1_8_8") (pintype "passive"))
      (node (ref "R2") (pin "2") (pinfunction "2_2") (pintype "passive"))
      (node (ref "R7") (pin "2") (pinfunction "2_2") (pintype "passive"))
      (node (ref "U1") (pin "6") (pinfunction "SENSTOP_6") (pintype "passive"))
    )
    (net (code "17") (name "/RNGSS") (class "Default")
      (node (ref "C30") (pin "1") (pinfunction "1_1") (pintype "passive"))
      (node (ref "E10") (pin "1") (pinfunction "A_1") (pintype "passive"))
      (node (ref "R31") (pin "1") (pinfunction "1_1") (pintype "passive"))
      (node (ref "U1") (pin "15") (pinfunction "RNG/SS_15") (pintype "passive"))
    )
    (net (code "18") (name "/RT") (class "Default")
      (node (ref "R32") (pin "1") (pinfunction "1_1") (pintype "passive"))
      (node (ref "U1") (pin "8") (pinfunction "RT_8") (pintype "passive"))
    )
    (net (code "19") (name "/SHDN") (class "Default")
      (node (ref "E3") (pin "1") (pinfunction "A_1") (pintype "passive"))
      (node (ref "R12") (pin "1") (pinfunction "1_1") (pintype "passive"))
      (node (ref "R8") (pin "2") (pinfunction "2_2") (pintype "passive"))
      (node (ref "U1") (pin "9") (pinfunction "SHDN_9") (pintype "passive"))
    )
    (net (code "20") (name "/SW1") (class "Default")
      (node (ref "C10") (pin "1") (pinfunction "1_1") (pintype "passive"))
      (node (ref "C17") (pin "2") (pinfunction "2_2") (pintype "passive"))
      (node (ref "D6") (pin "1") (pinfunction "C_1") (pintype "passive"))
      (node (ref "L1") (pin "1") (pinfunction "1_1") (pintype "passive"))
      (node (ref "Q1") (pin "1") (pinfunction "S1_1") (pintype "passive"))
      (node (ref "Q1") (pin "5") (pinfunction "D2_5_5") (pintype "passive"))
      (node (ref "Q1") (pin "6") (pinfunction "D2_6_6") (pintype "passive"))
      (node (ref "TP3") (pin "1") (pinfunction "1_1") (pintype "passive"))
      (node (ref "U1") (pin "38") (pinfunction "SW1_38") (pintype "passive"))
    )
    (net (code "21") (name "/SW2") (class "Default")
      (node (ref "C18") (pin "2") (pinfunction "2_2") (pintype "passive"))
      (node (ref "D4") (pin "2") (pinfunction "A_2") (pintype "passive"))
      (node (ref "Q2") (pin "3") (pinfunction "S2_3") (pintype "passive"))
      (node (ref "Q2") (pin "7") (pinfunction "D1_7_7") (pintype "passive"))
      (node (ref "Q2") (pin "8") (pinfunction "D1_8_8") (pintype "passive"))
      (node (ref "R14") (pin "2") (pinfunction "2_2") (pintype "passive"))
      (node (ref "R15") (pin "2") (pinfunction "2_2") (pintype "passive"))
      (node (ref "TP4") (pin "1") (pinfunction "1_1") (pintype "passive"))
      (node (ref "U1") (pin "32") (pinfunction "SW2_32") (pintype "passive"))
      (node (ref "Z2") (pin "2") (pinfunction "A_2") (pintype "passive"))
    )
    (net (code "22") (name "/TG1") (class "Default")
      (node (ref "R10") (pin "1") (pinfunction "1_1") (pintype "passive"))
      (node (ref "U1") (pin "1") (pinfunction "TG1_1") (pintype "passive"))
    )
    (net (code "23") (name "/TG2") (class "Default")
      (node (ref "R11") (pin "2") (pinfunction "2_2") (pintype "passive"))
      (node (ref "U1") (pin "31") (pinfunction "TG2_31") (pintype "passive"))
    )
    (net (code "24") (name "/TIMER") (class "Default")
      (node (ref "JP3") (pin "2") (pinfunction "2_2") (pintype "passive"))
      (node (ref "U1") (pin "14") (pinfunction "TIMER_14") (pintype "passive"))
    )
    (net (code "25") (name "/VC") (class "Default")
      (node (ref "C29") (pin "1") (pinfunction "1_1") (pintype "passive"))
      (node (ref "R37") (pin "1") (pinfunction "1_1") (pintype "passive"))
      (node (ref "TP19") (pin "1") (pinfunction "1_1") (pintype "passive"))
      (node (ref "U1") (pin "28") (pinfunction "VC_28") (pintype "passive"))
    )
    (net (code "26") (name "/VFB") (class "Default")
      (node (ref "C20") (pin "2") (pinfunction "2_2") (pintype "passive"))
      (node (ref "R21") (pin "2") (pinfunction "2_2") (pintype "passive"))
      (node (ref "R25") (pin "1") (pinfunction "1_1") (pintype "passive"))
      (node (ref "TP13") (pin "1") (pinfunction "1_1") (pintype "passive"))
      (node (ref "U1") (pin "17") (pinfunction "VFB_17") (pintype "passive"))
    )
    (net (code "27") (name "/VFBMAX") (class "Default")
      (node (ref "C21") (pin "2") (pinfunction "2_2") (pintype "passive"))
      (node (ref "R1") (pin "2") (pinfunction "2_2") (pintype "passive"))
      (node (ref "R22") (pin "2") (pinfunction "2_2") (pintype "passive"))
      (node (ref "R26") (pin "1") (pinfunction "1_1") (pintype "passive"))
      (node (ref "TP12") (pin "1") (pinfunction "1_1") (pintype "passive"))
      (node (ref "U1") (pin "26") (pinfunction "VFBMAX_26") (pintype "passive"))
    )
    (net (code "28") (name "/VFBMIN") (class "Default")
      (node (ref "R1") (pin "1") (pinfunction "1_1") (pintype "passive"))
      (node (ref "R20") (pin "2") (pinfunction "2_2") (pintype "passive"))
      (node (ref "R27") (pin "1") (pinfunction "1_1") (pintype "passive"))
      (node (ref "U1") (pin "19") (pinfunction "VFBMIN_19") (pintype "passive"))
    )
    (net (code "29") (name "/VIN") (class "Default")
      (node (ref "C2") (pin "1") (pinfunction "1_1") (pintype "passive"))
      (node (ref "C4") (pin "1") (pinfunction "1_1") (pintype "passive"))
      (node (ref "C5") (pin "1") (pinfunction "1_1") (pintype "passive"))
      (node (ref "C6") (pin "1") (pinfunction "1_1") (pintype "passive"))
      (node (ref "C7") (pin "1") (pinfunction "1_1") (pintype "passive"))
      (node (ref "E1") (pin "1") (pinfunction "1_1") (pintype "passive"))
      (node (ref "J1") (pin "1") (pinfunction "1_1") (pintype "passive"))
      (node (ref "R2") (pin "1") (pinfunction "1_1") (pintype "passive"))
      (node (ref "R3") (pin "1") (pinfunction "1_1") (pintype "passive"))
      (node (ref "R8") (pin "1") (pinfunction "1_1") (pintype "passive"))
      (node (ref "R9") (pin "1") (pinfunction "1_1") (pintype "passive"))
      (node (ref "U1") (pin "7") (pinfunction "SENSVIN_7") (pintype "passive"))
    )
    (net (code "30") (name "/VINREG") (class "Default")
      (node (ref "R13") (pin "1") (pinfunction "1_1") (pintype "passive"))
      (node (ref "R9") (pin "2") (pinfunction "2_2") (pintype "passive"))
      (node (ref "U1") (pin "10") (pinfunction "VIN_REG_10") (pintype "passive"))
    )
    (net (code "31") (name "/VOUT") (class "Default")
      (node (ref "C12") (pin "1") (pinfunction "1_1") (pintype "passive"))
      (node (ref "C13") (pin "1") (pinfunction "1_1") (pintype "passive"))
      (node (ref "C14") (pin "1") (pinfunction "1_1") (pintype "passive"))
      (node (ref "C15") (pin "1") (pinfunction "1_1") (pintype "passive"))
      (node (ref "C9") (pin "1") (pinfunction "1_1") (pintype "passive"))
      (node (ref "D4") (pin "1") (pinfunction "C_1") (pintype "passive"))
      (node (ref "E4") (pin "1") (pinfunction "1_1") (pintype "passive"))
      (node (ref "J3") (pin "1") (pinfunction "1_1") (pintype "passive"))
      (node (ref "Q2") (pin "5") (pinfunction "D2_5_5") (pintype "passive"))
      (node (ref "Q2") (pin "6") (pinfunction "D2_6_6") (pintype "passive"))
      (node (ref "R17") (pin "1") (pinfunction "1_1") (pintype "passive"))
      (node (ref "R20") (pin "1") (pinfunction "1_1") (pintype "passive"))
      (node (ref "R34") (pin "1") (pinfunction "1_1") (pintype "passive"))
      (node (ref "R6") (pin "2") (pinfunction "2_2") (pintype "passive"))
      (node (ref "TP6") (pin "1") (pinfunction "1_1") (pintype "passive"))
    )
    (net (code "32") (name "GND_POWER") (class "Default")
      (node (ref "C11") (pin "2") (pinfunction "2_2") (pintype "passive"))
      (node (ref "C12") (pin "2") (pinfunction "2_2") (pintype "passive"))
      (node (ref "C13") (pin "2") (pinfunction "2_2") (pintype "passive"))
      (node (ref "C14") (pin "2") (pinfunction "2_2") (pintype "passive"))
      (node (ref "C15") (pin "2") (pinfunction "2_2") (pintype "passive"))
      (node (ref "C16") (pin "2") (pinfunction "2_2") (pintype "passive"))
      (node (ref "C19") (pin "1") (pinfunction "1_1") (pintype "passive"))
      (node (ref "C2") (pin "2") (pinfunction "2_2") (pintype "passive"))
      (node (ref "C3") (pin "2") (pinfunction "2_2") (pintype "passive"))
      (node (ref "C4") (pin "2") (pinfunction "2_2") (pintype "passive"))
      (node (ref "C5") (pin "2") (pinfunction "2_2") (pintype "passive"))
      (node (ref "C6") (pin "2") (pinfunction "2_2") (pintype "passive"))
      (node (ref "C7") (pin "2") (pinfunction "2_2") (pintype "passive"))
      (node (ref "C9") (pin "2") (pinfunction "2_2") (pintype "passive"))
      (node (ref "E12") (pin "1") (pinfunction "1_1") (pintype "passive"))
      (node (ref "E14") (pin "1") (pinfunction "1_1") (pintype "passive"))
      (node (ref "E2") (pin "1") (pinfunction "1_1") (pintype "passive"))
      (node (ref "E5") (pin "1") (pinfunction "1_1") (pintype "passive"))
      (node (ref "J2") (pin "1") (pinfunction "1_1") (pintype "passive"))
      (node (ref "J4") (pin "1") (pinfunction "1_1") (pintype "passive"))
      (node (ref "J6") (pin "1") (pinfunction "1_1") (pintype "passive"))
      (node (ref "Q2") (pin "1") (pinfunction "S1_1") (pintype "passive"))
      (node (ref "R23") (pin "2") (pinfunction "2_2") (pintype "passive"))
      (node (ref "R30") (pin "2") (pinfunction "2_2") (pintype "passive"))
      (node (ref "TP1") (pin "1") (pinfunction "1_1") (pintype "passive"))
      (node (ref "TP2") (pin "1") (pinfunction "1_1") (pintype "passive"))
      (node (ref "U1") (pin "35") (pinfunction "PGND_35") (pintype "passive"))
      (node (ref "U1") (pin "4") (pinfunction "SENSGND_4") (pintype "passive"))
    )
    (net (code "33") (name "GND_SIGNAL") (class "Default")
      (node (ref "C22") (pin "2") (pinfunction "2_2") (pintype "passive"))
      (node (ref "C23") (pin "2") (pinfunction "2_2") (pintype "passive"))
      (node (ref "C27") (pin "2") (pinfunction "2_2") (pintype "passive"))
      (node (ref "C28") (pin "2") (pinfunction "2_2") (pintype "passive"))
      (node (ref "C29") (pin "2") (pinfunction "2_2") (pintype "passive"))
      (node (ref "C30") (pin "2") (pinfunction "2_2") (pintype "passive"))
      (node (ref "C31") (pin "2") (pinfunction "2_2") (pintype "passive"))
      (node (ref "C32") (pin "2") (pinfunction "2_2") (pintype "passive"))
      (node (ref "E8") (pin "1") (pinfunction "A_1") (pintype "passive"))
      (node (ref "E9") (pin "1") (pinfunction "A_1") (pintype "passive"))
      (node (ref "JP1") (pin "4") (pinfunction "4_4") (pintype "passive"))
      (node (ref "JP2") (pin "5") (pinfunction "5_5") (pintype "passive"))
      (node (ref "JP3") (pin "3") (pinfunction "3_3") (pintype "passive"))
      (node (ref "R12") (pin "2") (pinfunction "2_2") (pintype "passive"))
      (node (ref "R13") (pin "2") (pinfunction "2_2") (pintype "passive"))
      (node (ref "R24") (pin "2") (pinfunction "2_2") (pintype "passive"))
      (node (ref "R29") (pin "2") (pinfunction "2_2") (pintype "passive"))
      (node (ref "R31") (pin "2") (pinfunction "2_2") (pintype "passive"))
      (node (ref "R32") (pin "2") (pinfunction "2_2") (pintype "passive"))
      (node (ref "TP20") (pin "1") (pinfunction "1_1") (pintype "passive"))
      (node (ref "TP21") (pin "1") (pinfunction "1_1") (pintype "passive"))
      (node (ref "TP22") (pin "1") (pinfunction "1_1") (pintype "passive"))
      (node (ref "U1") (pin "29") (pinfunction "SGND_29") (pintype "passive"))
      (node (ref "U1") (pin "3") (pinfunction "SGND_3") (pintype "passive"))
      (node (ref "U1") (pin "39") (pinfunction "SGND_39") (pintype "passive"))
    )
    (net (code "34") (name "Net-(C8-Pad2)") (class "Default")
      (node (ref "C8") (pin "2") (pinfunction "2_2") (pintype "passive"))
      (node (ref "R30") (pin "1") (pinfunction "1_1") (pintype "passive"))
    )
    (net (code "35") (name "Net-(C10-Pad2)") (class "Default")
      (node (ref "C10") (pin "2") (pinfunction "2_2") (pintype "passive"))
      (node (ref "R7") (pin "1") (pinfunction "1_1") (pintype "passive"))
    )
    (net (code "36") (name "Net-(C19-Pad2)") (class "Default")
      (node (ref "C19") (pin "2") (pinfunction "2_2") (pintype "passive"))
      (node (ref "R15") (pin "1") (pinfunction "1_1") (pintype "passive"))
    )
    (net (code "37") (name "Net-(C20-Pad1)") (class "Default")
      (node (ref "C20") (pin "1") (pinfunction "1_1") (pintype "passive"))
      (node (ref "R16") (pin "2") (pinfunction "2_2") (pintype "passive"))
      (node (ref "R21") (pin "1") (pinfunction "1_1") (pintype "passive"))
      (node (ref "TP9") (pin "1") (pinfunction "1_1") (pintype "passive"))
    )
    (net (code "38") (name "Net-(C21-Pad1)") (class "Default")
      (node (ref "C21") (pin "1") (pinfunction "1_1") (pintype "passive"))
      (node (ref "R17") (pin "2") (pinfunction "2_2") (pintype "passive"))
      (node (ref "R22") (pin "1") (pinfunction "1_1") (pintype "passive"))
      (node (ref "TP10") (pin "1") (pinfunction "1_1") (pintype "passive"))
    )
    (net (code "39") (name "Net-(C22-Pad1)") (class "Default")
      (node (ref "C22") (pin "1") (pinfunction "1_1") (pintype "passive"))
      (node (ref "JP3") (pin "1") (pinfunction "1_1") (pintype "passive"))
    )
    (net (code "40") (name "Net-(C24-Pad2)") (class "Default")
      (node (ref "C24") (pin "2") (pinfunction "2_2") (pintype "passive"))
      (node (ref "R35") (pin "1") (pinfunction "1_1") (pintype "passive"))
    )
    (net (code "41") (name "Net-(C25-Pad1)") (class "Default")
      (node (ref "C25") (pin "1") (pinfunction "1_1") (pintype "passive"))
      (node (ref "R28") (pin "2") (pinfunction "2_2") (pintype "passive"))
    )
    (net (code "42") (name "Net-(C28-Pad1)") (class "Default")
      (node (ref "C28") (pin "1") (pinfunction "1_1") (pintype "passive"))
      (node (ref "R36") (pin "2") (pinfunction "2_2") (pintype "passive"))
    )
    (net (code "43") (name "Net-(C32-Pad1)") (class "Default")
      (node (ref "C32") (pin "1") (pinfunction "1_1") (pintype "passive"))
      (node (ref "R37") (pin "2") (pinfunction "2_2") (pintype "passive"))
    )
    (net (code "44") (name "Net-(D3-ANODE)") (class "Default")
      (node (ref "D3") (pin "2") (pinfunction "ANODE_2") (pintype "passive"))
      (node (ref "R5") (pin "2") (pinfunction "2_2") (pintype "passive"))
    )
    (net (code "45") (name "Net-(D3-CATHODE)") (class "Default")
      (node (ref "D3") (pin "1") (pinfunction "CATHODE_1") (pintype "passive"))
      (node (ref "U1") (pin "12") (pinfunction "STAT1_12") (pintype "passive"))
    )
    (net (code "46") (name "Net-(D5-ANODE)") (class "Default")
      (node (ref "D5") (pin "2") (pinfunction "ANODE_2") (pintype "passive"))
      (node (ref "R4") (pin "2") (pinfunction "2_2") (pintype "passive"))
    )
    (net (code "47") (name "Net-(D5-CATHODE)") (class "Default")
      (node (ref "D5") (pin "1") (pinfunction "CATHODE_1") (pintype "passive"))
      (node (ref "U1") (pin "13") (pinfunction "STAT2_13") (pintype "passive"))
    )
    (net (code "48") (name "Net-(D6-A)") (class "Default")
      (node (ref "C16") (pin "1") (pinfunction "1_1") (pintype "passive"))
      (node (ref "D6") (pin "2") (pinfunction "A_2") (pintype "passive"))
      (node (ref "Q1") (pin "3") (pinfunction "S2_3") (pintype "passive"))
      (node (ref "R23") (pin "1") (pinfunction "1_1") (pintype "passive"))
      (node (ref "U1") (pin "5") (pinfunction "SENSBOT_5") (pintype "passive"))
    )
    (net (code "49") (name "Net-(E6-A)") (class "Default")
      (node (ref "E6") (pin "1") (pinfunction "A_1") (pintype "passive"))
      (node (ref "JP2") (pin "1") (pinfunction "1_1") (pintype "passive"))
    )
    (net (code "50") (name "Net-(JP2-Pad3)") (class "Default")
      (node (ref "JP2") (pin "3") (pinfunction "3_3") (pintype "passive"))
      (node (ref "R29") (pin "1") (pinfunction "1_1") (pintype "passive"))
    )
    (net (code "51") (name "Net-(L1-Pad2)") (class "Default")
      (node (ref "L1") (pin "2") (pinfunction "2_2") (pintype "passive"))
      (node (ref "R14") (pin "1") (pinfunction "1_1") (pintype "passive"))
    )
    (net (code "52") (name "Net-(Q1A-G1)") (class "Default")
      (node (ref "Q1") (pin "2") (pinfunction "G1_2") (pintype "passive"))
      (node (ref "R10") (pin "2") (pinfunction "2_2") (pintype "passive"))
    )
    (net (code "53") (name "Net-(Q1B-G2)") (class "Default")
      (node (ref "Q1") (pin "4") (pinfunction "G2_4") (pintype "passive"))
      (node (ref "R18") (pin "2") (pinfunction "2_2") (pintype "passive"))
    )
    (net (code "54") (name "Net-(Q2A-G1)") (class "Default")
      (node (ref "Q2") (pin "2") (pinfunction "G1_2") (pintype "passive"))
      (node (ref "R19") (pin "1") (pinfunction "1_1") (pintype "passive"))
    )
    (net (code "55") (name "Net-(Q2B-G2)") (class "Default")
      (node (ref "Q2") (pin "4") (pinfunction "G2_4") (pintype "passive"))
      (node (ref "R11") (pin "1") (pinfunction "1_1") (pintype "passive"))
    )
    (net (code "56") (name "Net-(Q3-S_1)") (class "Default")
      (node (ref "C26") (pin "1") (pinfunction "1_1") (pintype "passive"))
      (node (ref "Q3") (pin "1") (pinfunction "S_1_1") (pintype "passive"))
      (node (ref "Q3") (pin "2") (pinfunction "S_2_2") (pintype "passive"))
      (node (ref "Q3") (pin "3") (pinfunction "S_3_3") (pintype "passive"))
      (node (ref "R33") (pin "2") (pinfunction "2_2") (pintype "passive"))
      (node (ref "R34") (pin "2") (pinfunction "2_2") (pintype "passive"))
      (node (ref "TP16") (pin "1") (pinfunction "1_1") (pintype "passive"))
      (node (ref "Z1") (pin "3") (pinfunction "C_3") (pintype "passive"))
    )
    (net (code "57") (name "Net-(U1-PVIN)") (class "Default")
      (node (ref "C11") (pin "1") (pinfunction "1_1") (pintype "passive"))
      (node (ref "R3") (pin "2") (pinfunction "2_2") (pintype "passive"))
      (node (ref "U1") (pin "36") (pinfunction "PVIN_36") (pintype "passive"))
    )
  )
)
